# dimmerPower6.net
KiCad netlist of a schematic drawn in EAGLE
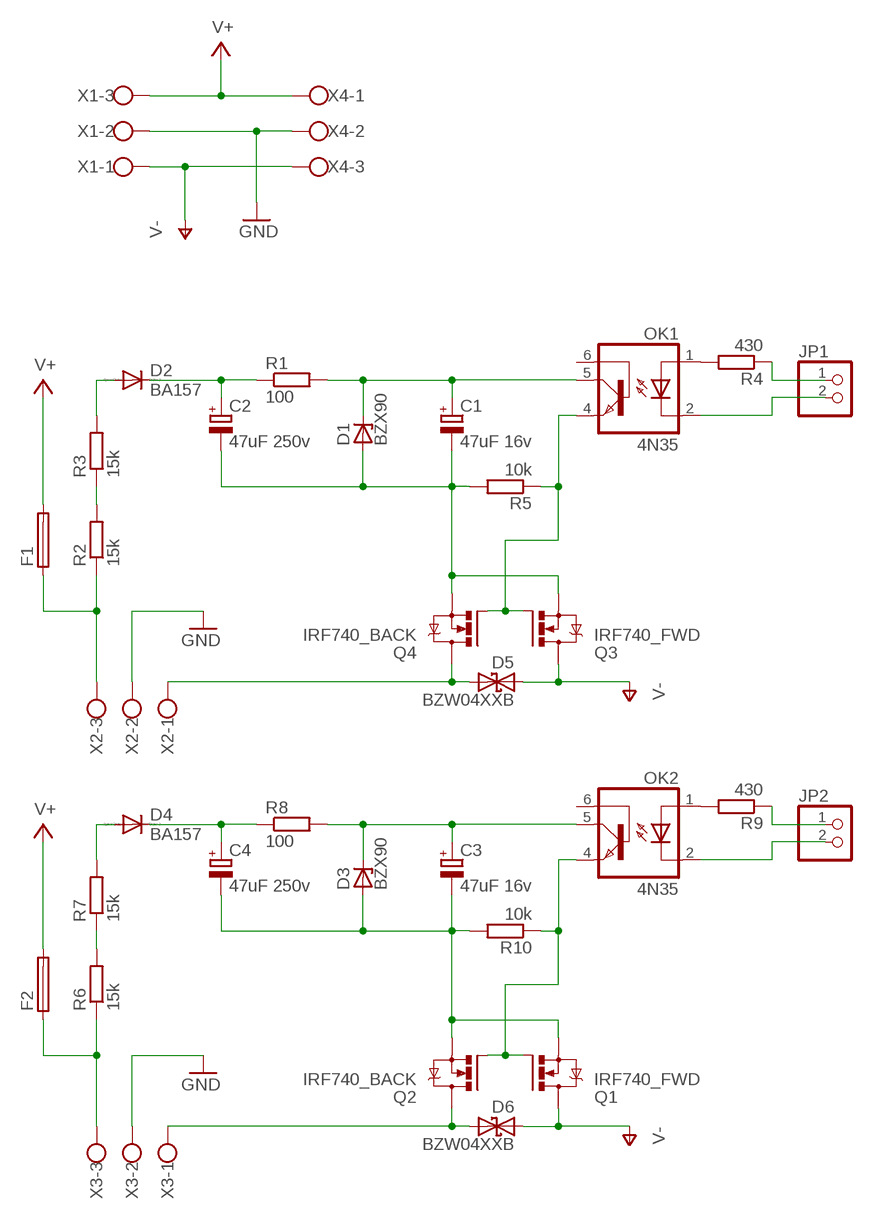
[diagram p0: schematic, sheet 1]

(export (version "E")
  (design (tool "Eeschema 10.0.6"))
  (components
    (comp (ref "C1")
      (value "47uF 16v")
      (footprint "eagle-import:E2,5-6")
      (libsource (lib "eagle-import") (part "CPOL-EUE2.5-6"))
    )
    (comp (ref "C2")
      (value "47uF 250v")
      (footprint "eagle-import:E5-13")
      (libsource (lib "eagle-import") (part "CPOL-EUE5-13"))
    )
    (comp (ref "C3")
      (value "47uF 16v")
      (footprint "eagle-import:E2,5-6")
      (libsource (lib "eagle-import") (part "CPOL-EUE2.5-6"))
    )
    (comp (ref "C4")
      (value "47uF 250v")
      (footprint "eagle-import:E5-13")
      (libsource (lib "eagle-import") (part "CPOL-EUE5-13"))
    )
    (comp (ref "D1")
      (value "BZX90")
      (footprint "eagle-import:DO34Z7")
      (libsource (lib "eagle-import") (part "BZX90"))
    )
    (comp (ref "D2")
      (value "BA157")
      (footprint "eagle-import:P1-10")
      (libsource (lib "eagle-import") (part "BA157"))
    )
    (comp (ref "D3")
      (value "BZX90")
      (footprint "eagle-import:DO34Z7")
      (libsource (lib "eagle-import") (part "BZX90"))
    )
    (comp (ref "D4")
      (value "BA157")
      (footprint "eagle-import:P1-10")
      (libsource (lib "eagle-import") (part "BA157"))
    )
    (comp (ref "D5")
      (value "BZW04XXB")
      (footprint "eagle-import:F126Z12")
      (libsource (lib "eagle-import") (part "BZW04XXB"))
    )
    (comp (ref "D6")
      (value "BZW04XXB")
      (footprint "eagle-import:F126Z12")
      (libsource (lib "eagle-import") (part "BZW04XXB"))
    )
    (comp (ref "F1")
      (value "SH22,5")
      (footprint "eagle-import:SH22,5")
      (fields (field (name "MF") "SCHURTER") (field (name "MPN") "0031.8201"))
      (libsource (lib "eagle-import") (part "SH22,5"))
    )
    (comp (ref "F2")
      (value "SH22,5")
      (footprint "eagle-import:SH22,5")
      (fields (field (name "MF") "SCHURTER") (field (name "MPN") "0031.8201"))
      (libsource (lib "eagle-import") (part "SH22,5"))
    )
    (comp (ref "JP1")
      (value "PINHD-1X2")
      (footprint "eagle-import:1X02")
      (libsource (lib "eagle-import") (part "PINHD-1X2"))
    )
    (comp (ref "JP2")
      (value "PINHD-1X2")
      (footprint "eagle-import:1X02")
      (libsource (lib "eagle-import") (part "PINHD-1X2"))
    )
    (comp (ref "OK1")
      (value "4N35")
      (footprint "eagle-import:DIL06")
      (fields (field (name "MF") "FAIRCHILD SEMICONDUCTOR"))
      (libsource (lib "eagle-import") (part "4N35"))
    )
    (comp (ref "OK2")
      (value "4N35")
      (footprint "eagle-import:DIL06")
      (fields (field (name "MF") "FAIRCHILD SEMICONDUCTOR"))
      (libsource (lib "eagle-import") (part "4N35"))
    )
    (comp (ref "Q1")
      (value "IRF740_FWD")
      (footprint "eagle-import:TO220BV_FWD")
      (libsource (lib "eagle-import") (part "IRF740_FWD"))
    )
    (comp (ref "Q2")
      (value "IRF740_BACK")
      (footprint "eagle-import:TO220BV_BACK")
      (libsource (lib "eagle-import") (part "IRF740_BACK"))
    )
    (comp (ref "Q3")
      (value "IRF740_FWD")
      (footprint "eagle-import:TO220BV_FWD")
      (libsource (lib "eagle-import") (part "IRF740_FWD"))
    )
    (comp (ref "Q4")
      (value "IRF740_BACK")
      (footprint "eagle-import:TO220BV_BACK")
      (libsource (lib "eagle-import") (part "IRF740_BACK"))
    )
    (comp (ref "R1")
      (value "100")
      (footprint "eagle-import:0204_7")
      (libsource (lib "eagle-import") (part "R-EU_0204/7"))
    )
    (comp (ref "R2")
      (value "15k")
      (footprint "eagle-import:P0613_15")
      (libsource (lib "eagle-import") (part "R-EU_0613/15"))
    )
    (comp (ref "R3")
      (value "15k")
      (footprint "eagle-import:P0613_15")
      (libsource (lib "eagle-import") (part "R-EU_0613/15"))
    )
    (comp (ref "R4")
      (value "430")
      (footprint "eagle-import:0204_7")
      (libsource (lib "eagle-import") (part "R-EU_0204/7"))
    )
    (comp (ref "R5")
      (value "10k")
      (footprint "eagle-import:0204_7")
      (libsource (lib "eagle-import") (part "R-EU_0204/7"))
    )
    (comp (ref "R6")
      (value "15k")
      (footprint "eagle-import:P0613_15")
      (libsource (lib "eagle-import") (part "R-EU_0613/15"))
    )
    (comp (ref "R7")
      (value "15k")
      (footprint "eagle-import:P0613_15")
      (libsource (lib "eagle-import") (part "R-EU_0613/15"))
    )
    (comp (ref "R8")
      (value "100")
      (footprint "eagle-import:0204_7")
      (libsource (lib "eagle-import") (part "R-EU_0204/7"))
    )
    (comp (ref "R9")
      (value "430")
      (footprint "eagle-import:0204_7")
      (libsource (lib "eagle-import") (part "R-EU_0204/7"))
    )
    (comp (ref "R10")
      (value "10k")
      (footprint "eagle-import:0204_7")
      (libsource (lib "eagle-import") (part "R-EU_0204/7"))
    )
    (comp (ref "X1")
      (value "W237-103")
      (footprint "eagle-import:W237-103")
      (fields (field (name "MPN") "237-103"))
      (libsource (lib "eagle-import") (part "W237-103"))
    )
    (comp (ref "X2")
      (value "W237-103")
      (footprint "eagle-import:W237-103")
      (fields (field (name "MPN") "237-103"))
      (libsource (lib "eagle-import") (part "W237-103"))
    )
    (comp (ref "X3")
      (value "W237-103")
      (footprint "eagle-import:W237-103")
      (fields (field (name "MPN") "237-103"))
      (libsource (lib "eagle-import") (part "W237-103"))
    )
    (comp (ref "X4")
      (value "W237-103")
      (footprint "eagle-import:W237-103")
      (fields (field (name "MPN") "237-103"))
      (libsource (lib "eagle-import") (part "W237-103"))
    )
  )
  (nets
    (net (code "1") (name "GND") (class "Default")
      (node (ref "X1") (pin "2") (pinfunction "KL_2") (pintype "passive"))
      (node (ref "X2") (pin "2") (pinfunction "KL_2") (pintype "passive"))
      (node (ref "X3") (pin "2") (pinfunction "KL_2") (pintype "passive"))
      (node (ref "X4") (pin "2") (pinfunction "KL_2") (pintype "passive"))
    )
    (net (code "2") (name "Net-(C1-Pad-)") (class "Default")
      (node (ref "C1") (pin "-") (pinfunction "-_-") (pintype "passive"))
      (node (ref "C2") (pin "-") (pinfunction "-_-") (pintype "passive"))
      (node (ref "D1") (pin "A") (pinfunction "A_A") (pintype "passive"))
      (node (ref "Q3") (pin "S") (pinfunction "S_S") (pintype "passive"))
      (node (ref "Q4") (pin "S") (pinfunction "S_S") (pintype "passive"))
      (node (ref "R5") (pin "2") (pinfunction "2_2") (pintype "passive"))
    )
    (net (code "3") (name "Net-(C2-Pad+)") (class "Default")
      (node (ref "C2") (pin "+") (pinfunction "+_+") (pintype "passive"))
      (node (ref "D2") (pin "C") (pinfunction "C_C") (pintype "passive"))
      (node (ref "R1") (pin "1") (pinfunction "1_1") (pintype "passive"))
    )
    (net (code "4") (name "Net-(C3-Pad-)") (class "Default")
      (node (ref "C3") (pin "-") (pinfunction "-_-") (pintype "passive"))
      (node (ref "C4") (pin "-") (pinfunction "-_-") (pintype "passive"))
      (node (ref "D3") (pin "A") (pinfunction "A_A") (pintype "passive"))
      (node (ref "Q1") (pin "S") (pinfunction "S_S") (pintype "passive"))
      (node (ref "Q2") (pin "S") (pinfunction "S_S") (pintype "passive"))
      (node (ref "R10") (pin "2") (pinfunction "2_2") (pintype "passive"))
    )
    (net (code "5") (name "Net-(C4-Pad+)") (class "Default")
      (node (ref "C4") (pin "+") (pinfunction "+_+") (pintype "passive"))
      (node (ref "D4") (pin "C") (pinfunction "C_C") (pintype "passive"))
      (node (ref "R8") (pin "1") (pinfunction "1_1") (pintype "passive"))
    )
    (net (code "6") (name "Net-(D2-PadA)") (class "Default")
      (node (ref "D2") (pin "A") (pinfunction "A_A") (pintype "passive"))
      (node (ref "R3") (pin "2") (pinfunction "2_2") (pintype "passive"))
    )
    (net (code "7") (name "Net-(D4-PadA)") (class "Default")
      (node (ref "D4") (pin "A") (pinfunction "A_A") (pintype "passive"))
      (node (ref "R7") (pin "2") (pinfunction "2_2") (pintype "passive"))
    )
    (net (code "8") (name "Net-(D5-2)") (class "Default")
      (node (ref "D5") (pin "C") (pinfunction "2_C") (pintype "passive"))
      (node (ref "Q4") (pin "D") (pinfunction "D_D") (pintype "passive"))
      (node (ref "X2") (pin "1") (pinfunction "KL_1") (pintype "passive"))
    )
    (net (code "9") (name "Net-(D6-2)") (class "Default")
      (node (ref "D6") (pin "C") (pinfunction "2_C") (pintype "passive"))
      (node (ref "Q2") (pin "D") (pinfunction "D_D") (pintype "passive"))
      (node (ref "X3") (pin "1") (pinfunction "KL_1") (pintype "passive"))
    )
    (net (code "10") (name "Net-(JP1-Pad1)") (class "Default")
      (node (ref "JP1") (pin "1") (pinfunction "1_1") (pintype "passive"))
      (node (ref "R4") (pin "1") (pinfunction "1_1") (pintype "passive"))
    )
    (net (code "11") (name "Net-(JP2-Pad1)") (class "Default")
      (node (ref "JP2") (pin "1") (pinfunction "1_1") (pintype "passive"))
      (node (ref "R9") (pin "1") (pinfunction "1_1") (pintype "passive"))
    )
    (net (code "12") (name "Net-(OK1-A)") (class "Default")
      (node (ref "OK1") (pin "1") (pinfunction "A_1") (pintype "passive"))
      (node (ref "R4") (pin "2") (pinfunction "2_2") (pintype "passive"))
    )
    (net (code "13") (name "Net-(OK1-C)") (class "Default")
      (node (ref "JP1") (pin "2") (pinfunction "2_2") (pintype "passive"))
      (node (ref "OK1") (pin "2") (pinfunction "C_2") (pintype "passive"))
    )
    (net (code "14") (name "Net-(OK1-COL)") (class "Default")
      (node (ref "C1") (pin "+") (pinfunction "+_+") (pintype "passive"))
      (node (ref "D1") (pin "C") (pinfunction "C_C") (pintype "passive"))
      (node (ref "OK1") (pin "5") (pinfunction "COL_5") (pintype "passive"))
      (node (ref "R1") (pin "2") (pinfunction "2_2") (pintype "passive"))
    )
    (net (code "15") (name "Net-(OK1-EMI)") (class "Default")
      (node (ref "OK1") (pin "4") (pinfunction "EMI_4") (pintype "passive"))
      (node (ref "Q3") (pin "G") (pinfunction "G_G") (pintype "passive"))
      (node (ref "Q4") (pin "G") (pinfunction "G_G") (pintype "passive"))
      (node (ref "R5") (pin "1") (pinfunction "1_1") (pintype "passive"))
    )
    (net (code "16") (name "Net-(OK2-A)") (class "Default")
      (node (ref "OK2") (pin "1") (pinfunction "A_1") (pintype "passive"))
      (node (ref "R9") (pin "2") (pinfunction "2_2") (pintype "passive"))
    )
    (net (code "17") (name "Net-(OK2-C)") (class "Default")
      (node (ref "JP2") (pin "2") (pinfunction "2_2") (pintype "passive"))
      (node (ref "OK2") (pin "2") (pinfunction "C_2") (pintype "passive"))
    )
    (net (code "18") (name "Net-(OK2-COL)") (class "Default")
      (node (ref "C3") (pin "+") (pinfunction "+_+") (pintype "passive"))
      (node (ref "D3") (pin "C") (pinfunction "C_C") (pintype "passive"))
      (node (ref "OK2") (pin "5") (pinfunction "COL_5") (pintype "passive"))
      (node (ref "R8") (pin "2") (pinfunction "2_2") (pintype "passive"))
    )
    (net (code "19") (name "Net-(OK2-EMI)") (class "Default")
      (node (ref "OK2") (pin "4") (pinfunction "EMI_4") (pintype "passive"))
      (node (ref "Q1") (pin "G") (pinfunction "G_G") (pintype "passive"))
      (node (ref "Q2") (pin "G") (pinfunction "G_G") (pintype "passive"))
      (node (ref "R10") (pin "1") (pinfunction "1_1") (pintype "passive"))
    )
    (net (code "20") (name "Net-(R2-Pad2)") (class "Default")
      (node (ref "R2") (pin "2") (pinfunction "2_2") (pintype "passive"))
      (node (ref "R3") (pin "1") (pinfunction "1_1") (pintype "passive"))
    )
    (net (code "21") (name "Net-(R6-Pad2)") (class "Default")
      (node (ref "R6") (pin "2") (pinfunction "2_2") (pintype "passive"))
      (node (ref "R7") (pin "1") (pinfunction "1_1") (pintype "passive"))
    )
    (net (code "22") (name "Net-(X2C-KL)") (class "Default")
      (node (ref "F1") (pin "1") (pinfunction "1_1") (pintype "passive"))
      (node (ref "R2") (pin "1") (pinfunction "1_1") (pintype "passive"))
      (node (ref "X2") (pin "3") (pinfunction "KL_3") (pintype "passive"))
    )
    (net (code "23") (name "Net-(X3C-KL)") (class "Default")
      (node (ref "F2") (pin "1") (pinfunction "1_1") (pintype "passive"))
      (node (ref "R6") (pin "1") (pinfunction "1_1") (pintype "passive"))
      (node (ref "X3") (pin "3") (pinfunction "KL_3") (pintype "passive"))
    )
    (net (code "24") (name "V+") (class "Default")
      (node (ref "F1") (pin "2") (pinfunction "2_2") (pintype "passive"))
      (node (ref "F2") (pin "2") (pinfunction "2_2") (pintype "passive"))
      (node (ref "X1") (pin "3") (pinfunction "KL_3") (pintype "passive"))
      (node (ref "X4") (pin "1") (pinfunction "KL_1") (pintype "passive"))
    )
    (net (code "25") (name "V-") (class "Default")
      (node (ref "D5") (pin "A") (pinfunction "1_A") (pintype "passive"))
      (node (ref "D6") (pin "A") (pinfunction "1_A") (pintype "passive"))
      (node (ref "Q1") (pin "D") (pinfunction "D_D") (pintype "passive"))
      (node (ref "Q3") (pin "D") (pinfunction "D_D") (pintype "passive"))
      (node (ref "X1") (pin "1") (pinfunction "KL_1") (pintype "passive"))
      (node (ref "X4") (pin "3") (pinfunction "KL_3") (pintype "passive"))
    )
    (net (code "26") (name "unconnected-(OK1-BAS-Pad6)") (class "Default")
      (node (ref "OK1") (pin "6") (pinfunction "BAS_6") (pintype "passive"))
    )
    (net (code "27") (name "unconnected-(OK2-BAS-Pad6)") (class "Default")
      (node (ref "OK2") (pin "6") (pinfunction "BAS_6") (pintype "passive"))
    )
  )
)
